# 16_ch_sample-and-hold_card_v3.net
KiCad netlist of a schematic drawn in EAGLE
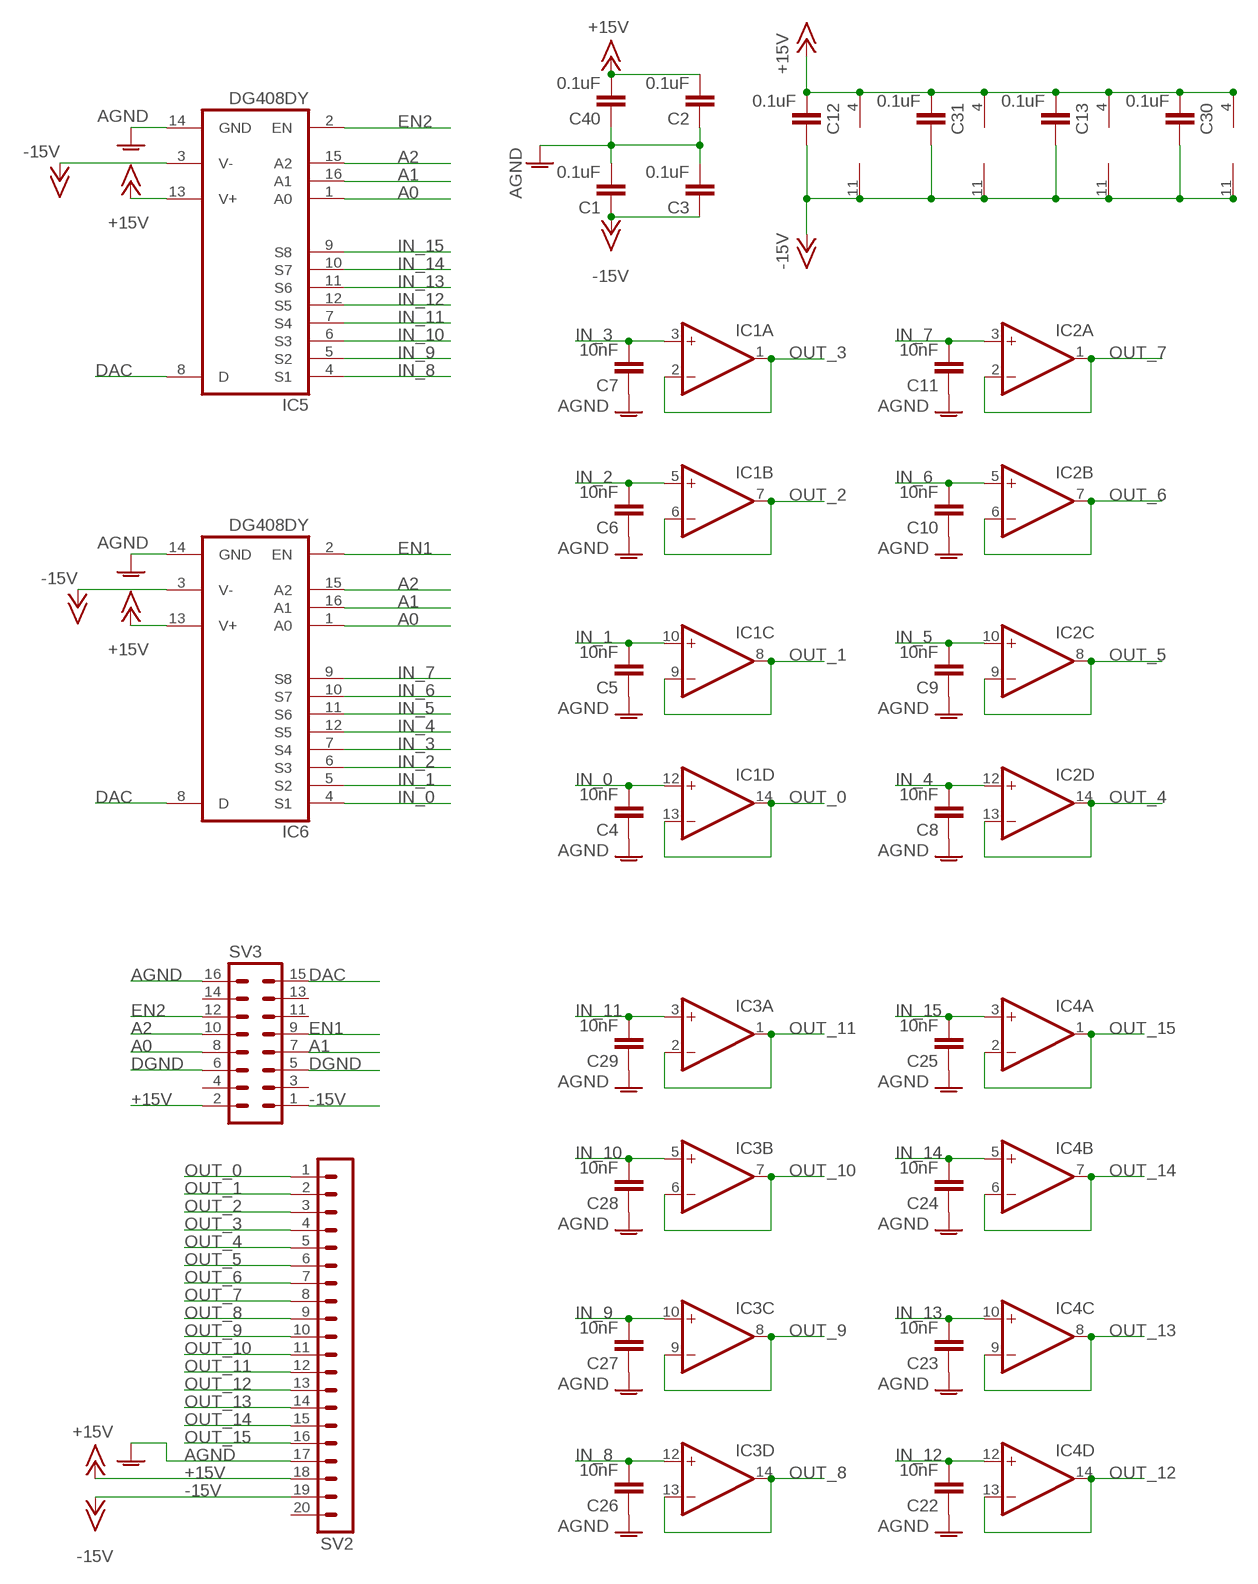
[diagram p0: schematic, sheet 1]

(export (version "E")
  (design (tool "Eeschema 10.0.6"))
  (components
    (comp (ref "C1")
      (value "0.1uF")
      (footprint "eagle-import:C0603")
      (libsource (lib "eagle-import") (part "C-EUC0603"))
    )
    (comp (ref "C2")
      (value "0.1uF")
      (footprint "eagle-import:C0603")
      (libsource (lib "eagle-import") (part "C-EUC0603"))
    )
    (comp (ref "C3")
      (value "0.1uF")
      (footprint "eagle-import:C0603")
      (libsource (lib "eagle-import") (part "C-EUC0603"))
    )
    (comp (ref "C4")
      (value "10nF")
      (footprint "eagle-import:C1206")
      (libsource (lib "eagle-import") (part "C-EUC1206"))
    )
    (comp (ref "C5")
      (value "10nF")
      (footprint "eagle-import:C1206")
      (libsource (lib "eagle-import") (part "C-EUC1206"))
    )
    (comp (ref "C6")
      (value "10nF")
      (footprint "eagle-import:C1206")
      (libsource (lib "eagle-import") (part "C-EUC1206"))
    )
    (comp (ref "C7")
      (value "10nF")
      (footprint "eagle-import:C1206")
      (libsource (lib "eagle-import") (part "C-EUC1206"))
    )
    (comp (ref "C8")
      (value "10nF")
      (footprint "eagle-import:C1206")
      (libsource (lib "eagle-import") (part "C-EUC1206"))
    )
    (comp (ref "C9")
      (value "10nF")
      (footprint "eagle-import:C1206")
      (libsource (lib "eagle-import") (part "C-EUC1206"))
    )
    (comp (ref "C10")
      (value "10nF")
      (footprint "eagle-import:C1206")
      (libsource (lib "eagle-import") (part "C-EUC1206"))
    )
    (comp (ref "C11")
      (value "10nF")
      (footprint "eagle-import:C1206")
      (libsource (lib "eagle-import") (part "C-EUC1206"))
    )
    (comp (ref "C12")
      (value "0.1uF")
      (footprint "eagle-import:C0603")
      (libsource (lib "eagle-import") (part "C-EUC0603"))
    )
    (comp (ref "C13")
      (value "0.1uF")
      (footprint "eagle-import:C0603")
      (libsource (lib "eagle-import") (part "C-EUC0603"))
    )
    (comp (ref "C22")
      (value "10nF")
      (footprint "eagle-import:C1206")
      (libsource (lib "eagle-import") (part "C-EUC1206"))
    )
    (comp (ref "C23")
      (value "10nF")
      (footprint "eagle-import:C1206")
      (libsource (lib "eagle-import") (part "C-EUC1206"))
    )
    (comp (ref "C24")
      (value "10nF")
      (footprint "eagle-import:C1206")
      (libsource (lib "eagle-import") (part "C-EUC1206"))
    )
    (comp (ref "C25")
      (value "10nF")
      (footprint "eagle-import:C1206")
      (libsource (lib "eagle-import") (part "C-EUC1206"))
    )
    (comp (ref "C26")
      (value "10nF")
      (footprint "eagle-import:C1206")
      (libsource (lib "eagle-import") (part "C-EUC1206"))
    )
    (comp (ref "C27")
      (value "10nF")
      (footprint "eagle-import:C1206")
      (libsource (lib "eagle-import") (part "C-EUC1206"))
    )
    (comp (ref "C28")
      (value "10nF")
      (footprint "eagle-import:C1206")
      (libsource (lib "eagle-import") (part "C-EUC1206"))
    )
    (comp (ref "C29")
      (value "10nF")
      (footprint "eagle-import:C1206")
      (libsource (lib "eagle-import") (part "C-EUC1206"))
    )
    (comp (ref "C30")
      (value "0.1uF")
      (footprint "eagle-import:C0603")
      (libsource (lib "eagle-import") (part "C-EUC0603"))
    )
    (comp (ref "C31")
      (value "0.1uF")
      (footprint "eagle-import:C0603")
      (libsource (lib "eagle-import") (part "C-EUC0603"))
    )
    (comp (ref "C40")
      (value "0.1uF")
      (footprint "eagle-import:C0603")
      (libsource (lib "eagle-import") (part "C-EUC0603"))
    )
    (comp (ref "IC1")
      (value "TL074D")
      (footprint "eagle-import:SO14")
      (libsource (lib "eagle-import") (part "TL074D"))
    )
    (comp (ref "IC2")
      (value "TL074D")
      (footprint "eagle-import:SO14")
      (libsource (lib "eagle-import") (part "TL074D"))
    )
    (comp (ref "IC3")
      (value "TL074D")
      (footprint "eagle-import:SO14")
      (libsource (lib "eagle-import") (part "TL074D"))
    )
    (comp (ref "IC4")
      (value "TL074D")
      (footprint "eagle-import:SO14")
      (libsource (lib "eagle-import") (part "TL074D"))
    )
    (comp (ref "IC5")
      (value "DG408DY")
      (footprint "eagle-import:SO16")
      (fields (field (name "MPN") "DG408DY+T"))
      (libsource (lib "eagle-import") (part "DG408DY"))
    )
    (comp (ref "IC6")
      (value "DG408DY")
      (footprint "eagle-import:SO16")
      (fields (field (name "MPN") "DG408DY+T"))
      (libsource (lib "eagle-import") (part "DG408DY"))
    )
    (comp (ref "SV2")
      (value "MA20-1")
      (footprint "eagle-import:MA20-1")
      (libsource (lib "eagle-import") (part "MA20-1"))
    )
    (comp (ref "SV3")
      (value "MA08-2J")
      (footprint "eagle-import:MA08-2J")
      (libsource (lib "eagle-import") (part "MA08-2J"))
    )
  )
  (nets
    (net (code "1") (name "+15V") (class "Default")
      (node (ref "C12") (pin "1") (pinfunction "1_1") (pintype "passive"))
      (node (ref "C13") (pin "1") (pinfunction "1_1") (pintype "passive"))
      (node (ref "C2") (pin "2") (pinfunction "2_2") (pintype "passive"))
      (node (ref "C30") (pin "1") (pinfunction "1_1") (pintype "passive"))
      (node (ref "C31") (pin "1") (pinfunction "1_1") (pintype "passive"))
      (node (ref "C40") (pin "2") (pinfunction "2_2") (pintype "passive"))
      (node (ref "IC1") (pin "4") (pinfunction "V+_4") (pintype "power_in"))
      (node (ref "IC2") (pin "4") (pinfunction "V+_4") (pintype "power_in"))
      (node (ref "IC3") (pin "4") (pinfunction "V+_4") (pintype "power_in"))
      (node (ref "IC4") (pin "4") (pinfunction "V+_4") (pintype "power_in"))
      (node (ref "IC5") (pin "13") (pinfunction "V+_13") (pintype "power_in"))
      (node (ref "IC6") (pin "13") (pinfunction "V+_13") (pintype "power_in"))
      (node (ref "SV2") (pin "18") (pinfunction "18_18") (pintype "passive"))
      (node (ref "SV3") (pin "2") (pinfunction "2_2") (pintype "passive"))
    )
    (net (code "2") (name "-15V") (class "Default")
      (node (ref "C1") (pin "1") (pinfunction "1_1") (pintype "passive"))
      (node (ref "C12") (pin "2") (pinfunction "2_2") (pintype "passive"))
      (node (ref "C13") (pin "2") (pinfunction "2_2") (pintype "passive"))
      (node (ref "C3") (pin "1") (pinfunction "1_1") (pintype "passive"))
      (node (ref "C30") (pin "2") (pinfunction "2_2") (pintype "passive"))
      (node (ref "C31") (pin "2") (pinfunction "2_2") (pintype "passive"))
      (node (ref "IC1") (pin "11") (pinfunction "V-_11") (pintype "power_in"))
      (node (ref "IC2") (pin "11") (pinfunction "V-_11") (pintype "power_in"))
      (node (ref "IC3") (pin "11") (pinfunction "V-_11") (pintype "power_in"))
      (node (ref "IC4") (pin "11") (pinfunction "V-_11") (pintype "power_in"))
      (node (ref "IC5") (pin "3") (pinfunction "V-_3") (pintype "power_in"))
      (node (ref "IC6") (pin "3") (pinfunction "V-_3") (pintype "power_in"))
      (node (ref "SV2") (pin "19") (pinfunction "19_19") (pintype "passive"))
      (node (ref "SV3") (pin "1") (pinfunction "1_1") (pintype "passive"))
    )
    (net (code "3") (name "/A0") (class "Default")
      (node (ref "IC5") (pin "1") (pinfunction "A0_1") (pintype "input"))
      (node (ref "IC6") (pin "1") (pinfunction "A0_1") (pintype "input"))
      (node (ref "SV3") (pin "8") (pinfunction "8_8") (pintype "passive"))
    )
    (net (code "4") (name "/A1") (class "Default")
      (node (ref "IC5") (pin "16") (pinfunction "A1_16") (pintype "input"))
      (node (ref "IC6") (pin "16") (pinfunction "A1_16") (pintype "input"))
      (node (ref "SV3") (pin "7") (pinfunction "7_7") (pintype "passive"))
    )
    (net (code "5") (name "/A2") (class "Default")
      (node (ref "IC5") (pin "15") (pinfunction "A2_15") (pintype "input"))
      (node (ref "IC6") (pin "15") (pinfunction "A2_15") (pintype "input"))
      (node (ref "SV3") (pin "10") (pinfunction "10_10") (pintype "passive"))
    )
    (net (code "6") (name "/DAC") (class "Default")
      (node (ref "IC5") (pin "8") (pinfunction "D_8") (pintype "passive"))
      (node (ref "IC6") (pin "8") (pinfunction "D_8") (pintype "passive"))
      (node (ref "SV3") (pin "15") (pinfunction "15_15") (pintype "passive"))
    )
    (net (code "7") (name "/DGND") (class "Default")
      (node (ref "SV3") (pin "5") (pinfunction "5_5") (pintype "passive"))
      (node (ref "SV3") (pin "6") (pinfunction "6_6") (pintype "passive"))
    )
    (net (code "8") (name "/EN1") (class "Default")
      (node (ref "IC6") (pin "2") (pinfunction "EN_2") (pintype "input"))
      (node (ref "SV3") (pin "9") (pinfunction "9_9") (pintype "passive"))
    )
    (net (code "9") (name "/EN2") (class "Default")
      (node (ref "IC5") (pin "2") (pinfunction "EN_2") (pintype "input"))
      (node (ref "SV3") (pin "12") (pinfunction "12_12") (pintype "passive"))
    )
    (net (code "10") (name "/IN_0") (class "Default")
      (node (ref "C4") (pin "2") (pinfunction "2_2") (pintype "passive"))
      (node (ref "IC1") (pin "12") (pinfunction "+IN_12") (pintype "input"))
      (node (ref "IC6") (pin "4") (pinfunction "S1_4") (pintype "passive"))
    )
    (net (code "11") (name "/IN_1") (class "Default")
      (node (ref "C5") (pin "2") (pinfunction "2_2") (pintype "passive"))
      (node (ref "IC1") (pin "10") (pinfunction "+IN_10") (pintype "input"))
      (node (ref "IC6") (pin "5") (pinfunction "S2_5") (pintype "passive"))
    )
    (net (code "12") (name "/IN_2") (class "Default")
      (node (ref "C6") (pin "2") (pinfunction "2_2") (pintype "passive"))
      (node (ref "IC1") (pin "5") (pinfunction "+IN_5") (pintype "input"))
      (node (ref "IC6") (pin "6") (pinfunction "S3_6") (pintype "passive"))
    )
    (net (code "13") (name "/IN_3") (class "Default")
      (node (ref "C7") (pin "2") (pinfunction "2_2") (pintype "passive"))
      (node (ref "IC1") (pin "3") (pinfunction "+IN_3") (pintype "input"))
      (node (ref "IC6") (pin "7") (pinfunction "S4_7") (pintype "passive"))
    )
    (net (code "14") (name "/IN_4") (class "Default")
      (node (ref "C8") (pin "2") (pinfunction "2_2") (pintype "passive"))
      (node (ref "IC2") (pin "12") (pinfunction "+IN_12") (pintype "input"))
      (node (ref "IC6") (pin "12") (pinfunction "S5_12") (pintype "passive"))
    )
    (net (code "15") (name "/IN_5") (class "Default")
      (node (ref "C9") (pin "2") (pinfunction "2_2") (pintype "passive"))
      (node (ref "IC2") (pin "10") (pinfunction "+IN_10") (pintype "input"))
      (node (ref "IC6") (pin "11") (pinfunction "S6_11") (pintype "passive"))
    )
    (net (code "16") (name "/IN_6") (class "Default")
      (node (ref "C10") (pin "2") (pinfunction "2_2") (pintype "passive"))
      (node (ref "IC2") (pin "5") (pinfunction "+IN_5") (pintype "input"))
      (node (ref "IC6") (pin "10") (pinfunction "S7_10") (pintype "passive"))
    )
    (net (code "17") (name "/IN_7") (class "Default")
      (node (ref "C11") (pin "2") (pinfunction "2_2") (pintype "passive"))
      (node (ref "IC2") (pin "3") (pinfunction "+IN_3") (pintype "input"))
      (node (ref "IC6") (pin "9") (pinfunction "S8_9") (pintype "passive"))
    )
    (net (code "18") (name "/IN_8") (class "Default")
      (node (ref "C26") (pin "2") (pinfunction "2_2") (pintype "passive"))
      (node (ref "IC3") (pin "12") (pinfunction "+IN_12") (pintype "input"))
      (node (ref "IC5") (pin "4") (pinfunction "S1_4") (pintype "passive"))
    )
    (net (code "19") (name "/IN_9") (class "Default")
      (node (ref "C27") (pin "2") (pinfunction "2_2") (pintype "passive"))
      (node (ref "IC3") (pin "10") (pinfunction "+IN_10") (pintype "input"))
      (node (ref "IC5") (pin "5") (pinfunction "S2_5") (pintype "passive"))
    )
    (net (code "20") (name "/IN_10") (class "Default")
      (node (ref "C28") (pin "2") (pinfunction "2_2") (pintype "passive"))
      (node (ref "IC3") (pin "5") (pinfunction "+IN_5") (pintype "input"))
      (node (ref "IC5") (pin "6") (pinfunction "S3_6") (pintype "passive"))
    )
    (net (code "21") (name "/IN_11") (class "Default")
      (node (ref "C29") (pin "2") (pinfunction "2_2") (pintype "passive"))
      (node (ref "IC3") (pin "3") (pinfunction "+IN_3") (pintype "input"))
      (node (ref "IC5") (pin "7") (pinfunction "S4_7") (pintype "passive"))
    )
    (net (code "22") (name "/IN_12") (class "Default")
      (node (ref "C22") (pin "2") (pinfunction "2_2") (pintype "passive"))
      (node (ref "IC4") (pin "12") (pinfunction "+IN_12") (pintype "input"))
      (node (ref "IC5") (pin "12") (pinfunction "S5_12") (pintype "passive"))
    )
    (net (code "23") (name "/IN_13") (class "Default")
      (node (ref "C23") (pin "2") (pinfunction "2_2") (pintype "passive"))
      (node (ref "IC4") (pin "10") (pinfunction "+IN_10") (pintype "input"))
      (node (ref "IC5") (pin "11") (pinfunction "S6_11") (pintype "passive"))
    )
    (net (code "24") (name "/IN_14") (class "Default")
      (node (ref "C24") (pin "2") (pinfunction "2_2") (pintype "passive"))
      (node (ref "IC4") (pin "5") (pinfunction "+IN_5") (pintype "input"))
      (node (ref "IC5") (pin "10") (pinfunction "S7_10") (pintype "passive"))
    )
    (net (code "25") (name "/IN_15") (class "Default")
      (node (ref "C25") (pin "2") (pinfunction "2_2") (pintype "passive"))
      (node (ref "IC4") (pin "3") (pinfunction "+IN_3") (pintype "input"))
      (node (ref "IC5") (pin "9") (pinfunction "S8_9") (pintype "passive"))
    )
    (net (code "26") (name "/OUT_0") (class "Default")
      (node (ref "IC1") (pin "13") (pinfunction "-IN_13") (pintype "input"))
      (node (ref "IC1") (pin "14") (pinfunction "OUT_14") (pintype "output"))
      (node (ref "SV2") (pin "1") (pinfunction "1_1") (pintype "passive"))
    )
    (net (code "27") (name "/OUT_1") (class "Default")
      (node (ref "IC1") (pin "8") (pinfunction "OUT_8") (pintype "output"))
      (node (ref "IC1") (pin "9") (pinfunction "-IN_9") (pintype "input"))
      (node (ref "SV2") (pin "2") (pinfunction "2_2") (pintype "passive"))
    )
    (net (code "28") (name "/OUT_2") (class "Default")
      (node (ref "IC1") (pin "6") (pinfunction "-IN_6") (pintype "input"))
      (node (ref "IC1") (pin "7") (pinfunction "OUT_7") (pintype "output"))
      (node (ref "SV2") (pin "3") (pinfunction "3_3") (pintype "passive"))
    )
    (net (code "29") (name "/OUT_3") (class "Default")
      (node (ref "IC1") (pin "1") (pinfunction "OUT_1") (pintype "output"))
      (node (ref "IC1") (pin "2") (pinfunction "-IN_2") (pintype "input"))
      (node (ref "SV2") (pin "4") (pinfunction "4_4") (pintype "passive"))
    )
    (net (code "30") (name "/OUT_4") (class "Default")
      (node (ref "IC2") (pin "13") (pinfunction "-IN_13") (pintype "input"))
      (node (ref "IC2") (pin "14") (pinfunction "OUT_14") (pintype "output"))
      (node (ref "SV2") (pin "5") (pinfunction "5_5") (pintype "passive"))
    )
    (net (code "31") (name "/OUT_5") (class "Default")
      (node (ref "IC2") (pin "8") (pinfunction "OUT_8") (pintype "output"))
      (node (ref "IC2") (pin "9") (pinfunction "-IN_9") (pintype "input"))
      (node (ref "SV2") (pin "6") (pinfunction "6_6") (pintype "passive"))
    )
    (net (code "32") (name "/OUT_6") (class "Default")
      (node (ref "IC2") (pin "6") (pinfunction "-IN_6") (pintype "input"))
      (node (ref "IC2") (pin "7") (pinfunction "OUT_7") (pintype "output"))
      (node (ref "SV2") (pin "7") (pinfunction "7_7") (pintype "passive"))
    )
    (net (code "33") (name "/OUT_7") (class "Default")
      (node (ref "IC2") (pin "1") (pinfunction "OUT_1") (pintype "output"))
      (node (ref "IC2") (pin "2") (pinfunction "-IN_2") (pintype "input"))
      (node (ref "SV2") (pin "8") (pinfunction "8_8") (pintype "passive"))
    )
    (net (code "34") (name "/OUT_8") (class "Default")
      (node (ref "IC3") (pin "13") (pinfunction "-IN_13") (pintype "input"))
      (node (ref "IC3") (pin "14") (pinfunction "OUT_14") (pintype "output"))
      (node (ref "SV2") (pin "9") (pinfunction "9_9") (pintype "passive"))
    )
    (net (code "35") (name "/OUT_9") (class "Default")
      (node (ref "IC3") (pin "8") (pinfunction "OUT_8") (pintype "output"))
      (node (ref "IC3") (pin "9") (pinfunction "-IN_9") (pintype "input"))
      (node (ref "SV2") (pin "10") (pinfunction "10_10") (pintype "passive"))
    )
    (net (code "36") (name "/OUT_10") (class "Default")
      (node (ref "IC3") (pin "6") (pinfunction "-IN_6") (pintype "input"))
      (node (ref "IC3") (pin "7") (pinfunction "OUT_7") (pintype "output"))
      (node (ref "SV2") (pin "11") (pinfunction "11_11") (pintype "passive"))
    )
    (net (code "37") (name "/OUT_11") (class "Default")
      (node (ref "IC3") (pin "1") (pinfunction "OUT_1") (pintype "output"))
      (node (ref "IC3") (pin "2") (pinfunction "-IN_2") (pintype "input"))
      (node (ref "SV2") (pin "12") (pinfunction "12_12") (pintype "passive"))
    )
    (net (code "38") (name "/OUT_12") (class "Default")
      (node (ref "IC4") (pin "13") (pinfunction "-IN_13") (pintype "input"))
      (node (ref "IC4") (pin "14") (pinfunction "OUT_14") (pintype "output"))
      (node (ref "SV2") (pin "13") (pinfunction "13_13") (pintype "passive"))
    )
    (net (code "39") (name "/OUT_13") (class "Default")
      (node (ref "IC4") (pin "8") (pinfunction "OUT_8") (pintype "output"))
      (node (ref "IC4") (pin "9") (pinfunction "-IN_9") (pintype "input"))
      (node (ref "SV2") (pin "14") (pinfunction "14_14") (pintype "passive"))
    )
    (net (code "40") (name "/OUT_14") (class "Default")
      (node (ref "IC4") (pin "6") (pinfunction "-IN_6") (pintype "input"))
      (node (ref "IC4") (pin "7") (pinfunction "OUT_7") (pintype "output"))
      (node (ref "SV2") (pin "15") (pinfunction "15_15") (pintype "passive"))
    )
    (net (code "41") (name "/OUT_15") (class "Default")
      (node (ref "IC4") (pin "1") (pinfunction "OUT_1") (pintype "output"))
      (node (ref "IC4") (pin "2") (pinfunction "-IN_2") (pintype "input"))
      (node (ref "SV2") (pin "16") (pinfunction "16_16") (pintype "passive"))
    )
    (net (code "42") (name "AGND") (class "Default")
      (node (ref "C1") (pin "2") (pinfunction "2_2") (pintype "passive"))
      (node (ref "C10") (pin "1") (pinfunction "1_1") (pintype "passive"))
      (node (ref "C11") (pin "1") (pinfunction "1_1") (pintype "passive"))
      (node (ref "C2") (pin "1") (pinfunction "1_1") (pintype "passive"))
      (node (ref "C22") (pin "1") (pinfunction "1_1") (pintype "passive"))
      (node (ref "C23") (pin "1") (pinfunction "1_1") (pintype "passive"))
      (node (ref "C24") (pin "1") (pinfunction "1_1") (pintype "passive"))
      (node (ref "C25") (pin "1") (pinfunction "1_1") (pintype "passive"))
      (node (ref "C26") (pin "1") (pinfunction "1_1") (pintype "passive"))
      (node (ref "C27") (pin "1") (pinfunction "1_1") (pintype "passive"))
      (node (ref "C28") (pin "1") (pinfunction "1_1") (pintype "passive"))
      (node (ref "C29") (pin "1") (pinfunction "1_1") (pintype "passive"))
      (node (ref "C3") (pin "2") (pinfunction "2_2") (pintype "passive"))
      (node (ref "C4") (pin "1") (pinfunction "1_1") (pintype "passive"))
      (node (ref "C40") (pin "1") (pinfunction "1_1") (pintype "passive"))
      (node (ref "C5") (pin "1") (pinfunction "1_1") (pintype "passive"))
      (node (ref "C6") (pin "1") (pinfunction "1_1") (pintype "passive"))
      (node (ref "C7") (pin "1") (pinfunction "1_1") (pintype "passive"))
      (node (ref "C8") (pin "1") (pinfunction "1_1") (pintype "passive"))
      (node (ref "C9") (pin "1") (pinfunction "1_1") (pintype "passive"))
      (node (ref "IC5") (pin "14") (pinfunction "GND_14") (pintype "power_in"))
      (node (ref "IC6") (pin "14") (pinfunction "GND_14") (pintype "power_in"))
      (node (ref "SV2") (pin "17") (pinfunction "17_17") (pintype "passive"))
      (node (ref "SV3") (pin "16") (pinfunction "16_16") (pintype "passive"))
    )
    (net (code "43") (name "unconnected-(SV2-Pad20)") (class "Default")
      (node (ref "SV2") (pin "20") (pinfunction "20_20") (pintype "passive"))
    )
    (net (code "44") (name "unconnected-(SV3-Pad3)") (class "Default")
      (node (ref "SV3") (pin "3") (pinfunction "3_3") (pintype "passive"))
    )
    (net (code "45") (name "unconnected-(SV3-Pad4)") (class "Default")
      (node (ref "SV3") (pin "4") (pinfunction "4_4") (pintype "passive"))
    )
    (net (code "46") (name "unconnected-(SV3-Pad11)") (class "Default")
      (node (ref "SV3") (pin "11") (pinfunction "11_11") (pintype "passive"))
    )
    (net (code "47") (name "unconnected-(SV3-Pad13)") (class "Default")
      (node (ref "SV3") (pin "13") (pinfunction "13_13") (pintype "passive"))
    )
    (net (code "48") (name "unconnected-(SV3-Pad14)") (class "Default")
      (node (ref "SV3") (pin "14") (pinfunction "14_14") (pintype "passive"))
    )
  )
)
